# noisemaker_3-0.net
KiCad netlist of a schematic drawn in EAGLE
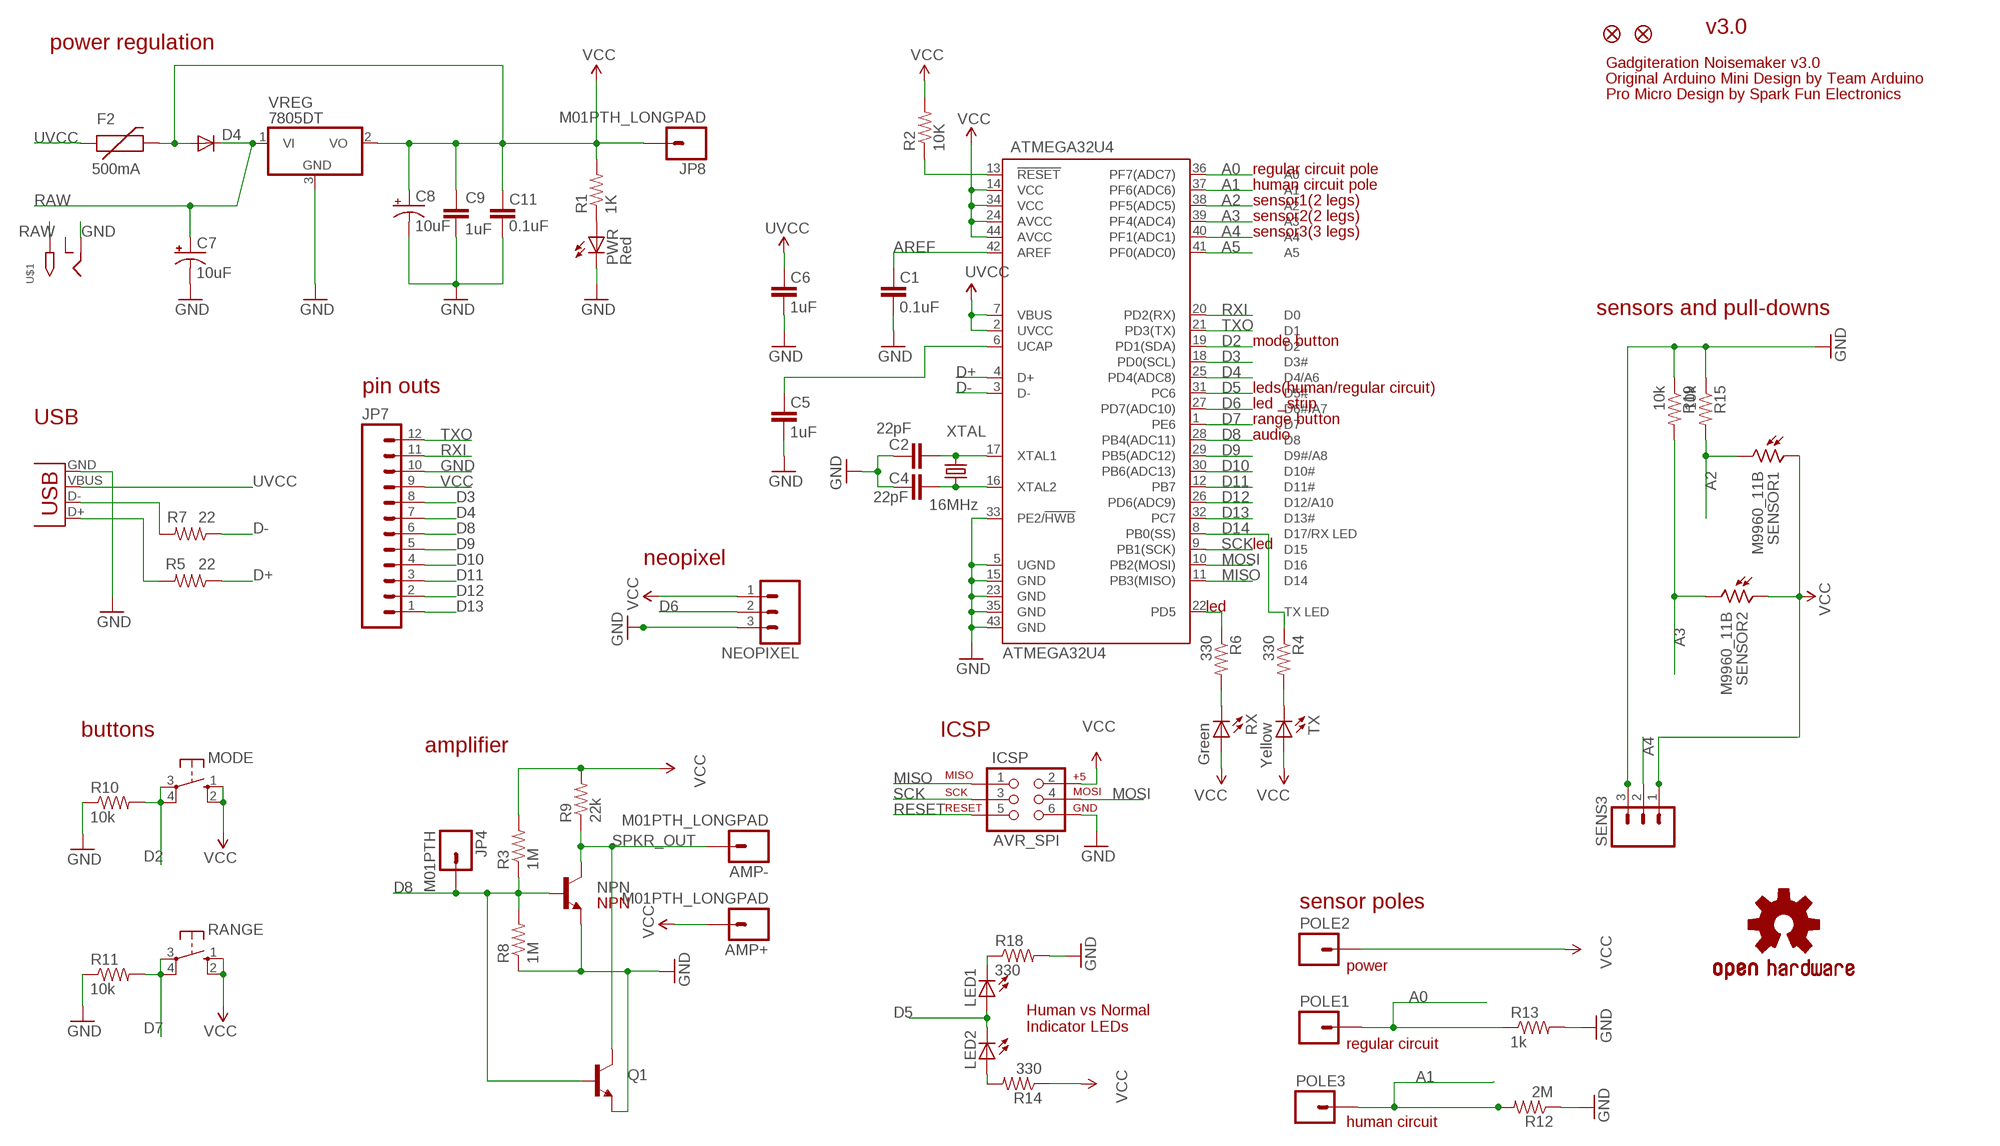
[diagram p0: schematic, sheet 1]

(export (version "E")
  (design (tool "Eeschema 10.0.6"))
  (components
    (comp (ref "AMP+")
      (value "M01PTH_LONGPAD")
      (footprint "eagle-import:1X01_LONGPAD")
      (libsource (lib "eagle-import") (part "M01PTH_LONGPAD"))
    )
    (comp (ref "AMP-")
      (value "M01PTH_LONGPAD")
      (footprint "eagle-import:1X01_LONGPAD")
      (libsource (lib "eagle-import") (part "M01PTH_LONGPAD"))
    )
    (comp (ref "ATMEGA32U4")
      (value "ATMEGA32U4")
      (footprint "eagle-import:SPARKFUN-DIGITALIC_TQFP44")
      (libsource (lib "eagle-import") (part "ATMEGA32U4TQFP"))
    )
    (comp (ref "C1")
      (value "0.1uF")
      (footprint "eagle-import:1206")
      (libsource (lib "eagle-import") (part "SparkFun-Capacitors_CAP1206"))
    )
    (comp (ref "C2")
      (value "22pF")
      (footprint "eagle-import:0603-CAP")
      (libsource (lib "eagle-import") (part "CAP0603-CAP"))
    )
    (comp (ref "C4")
      (value "22pF")
      (footprint "eagle-import:0603-CAP")
      (libsource (lib "eagle-import") (part "CAP0603-CAP"))
    )
    (comp (ref "C5")
      (value "1uF")
      (footprint "eagle-import:1206")
      (libsource (lib "eagle-import") (part "SparkFun-Capacitors_CAP1206"))
    )
    (comp (ref "C6")
      (value "1uF")
      (footprint "eagle-import:1206")
      (libsource (lib "eagle-import") (part "SparkFun-Capacitors_CAP1206"))
    )
    (comp (ref "C7")
      (value "10uF")
      (footprint "eagle-import:EIA3528-KIT")
      (libsource (lib "eagle-import") (part "CAP_POL3528-KIT"))
    )
    (comp (ref "C8")
      (value "10uF")
      (footprint "eagle-import:EIA3528-KIT")
      (libsource (lib "eagle-import") (part "CAP_POL3528-KIT"))
    )
    (comp (ref "C9")
      (value "1uF")
      (footprint "eagle-import:1206")
      (libsource (lib "eagle-import") (part "SparkFun-Capacitors_CAP1206"))
    )
    (comp (ref "C11")
      (value "0.1uF")
      (footprint "eagle-import:1206")
      (libsource (lib "eagle-import") (part "SparkFun-Capacitors_CAP1206"))
    )
    (comp (ref "D4")
      (value "DIODESOD")
      (footprint "eagle-import:SOD-323")
      (libsource (lib "eagle-import") (part "DIODESOD"))
    )
    (comp (ref "F2")
      (value "500mA")
      (footprint "eagle-import:PTC-1206")
      (libsource (lib "eagle-import") (part "PTCSMD"))
    )
    (comp (ref "ICSP")
      (value "AVR_SPI")
      (footprint "eagle-import:2X3")
      (libsource (lib "eagle-import") (part "AVR_SPI_PRG_6PTH"))
    )
    (comp (ref "JP1")
      (value "FIDUCIALUFIDUCIAL")
      (footprint "eagle-import:MICRO-FIDUCIAL")
      (libsource (lib "eagle-import") (part "FIDUCIALUFIDUCIAL"))
    )
    (comp (ref "JP2")
      (value "FIDUCIALUFIDUCIAL")
      (footprint "eagle-import:MICRO-FIDUCIAL")
      (libsource (lib "eagle-import") (part "FIDUCIALUFIDUCIAL"))
    )
    (comp (ref "JP3")
      (value "USB-B")
      (footprint "eagle-import:USB-B-PTH")
      (libsource (lib "eagle-import") (part "USBPTH"))
    )
    (comp (ref "JP4")
      (value "M01PTH")
      (footprint "eagle-import:1X01")
      (libsource (lib "eagle-import") (part "M01PTH"))
    )
    (comp (ref "JP7")
      (value "M12PTH")
      (footprint "eagle-import:1X12")
      (libsource (lib "eagle-import") (part "M12PTH"))
    )
    (comp (ref "JP8")
      (value "M01PTH_LONGPAD")
      (footprint "eagle-import:1X01_LONGPAD")
      (libsource (lib "eagle-import") (part "M01PTH_LONGPAD"))
    )
    (comp (ref "LED1")
      (value "LED3MM")
      (footprint "eagle-import:LED3MM")
      (libsource (lib "eagle-import") (part "LED3MM"))
    )
    (comp (ref "LED2")
      (value "LED3MM")
      (footprint "eagle-import:LED3MM")
      (libsource (lib "eagle-import") (part "LED3MM"))
    )
    (comp (ref "LOGO1")
      (value "OSHW-LOGOM")
      (footprint "eagle-import:OSHW-LOGO-M")
      (libsource (lib "eagle-import") (part "OSHW-LOGOM"))
    )
    (comp (ref "MODE")
      (value "10-XX")
      (footprint "eagle-import:B3F-10XX")
      (libsource (lib "eagle-import") (part "10-XX"))
    )
    (comp (ref "NEOPIXEL")
      (value "M03LONGPADS")
      (footprint "eagle-import:1X03_LONGPADS")
      (libsource (lib "eagle-import") (part "M03LONGPADS"))
    )
    (comp (ref "NPN")
      (value "TRANSISTOR_NPNSOT23-3")
      (footprint "eagle-import:SOT23-3")
      (libsource (lib "eagle-import") (part "TRANSISTOR_NPNSOT23-3"))
    )
    (comp (ref "POLE1")
      (value "M01PTH_LONGPAD")
      (footprint "eagle-import:1X01_LONGPAD")
      (libsource (lib "eagle-import") (part "M01PTH_LONGPAD"))
    )
    (comp (ref "POLE2")
      (value "M01PTH_LONGPAD")
      (footprint "eagle-import:1X01_LONGPAD")
      (libsource (lib "eagle-import") (part "M01PTH_LONGPAD"))
    )
    (comp (ref "POLE3")
      (value "M01PTH_LONGPAD")
      (footprint "eagle-import:1X01_LONGPAD")
      (libsource (lib "eagle-import") (part "M01PTH_LONGPAD"))
    )
    (comp (ref "PWR")
      (value "Red")
      (footprint "eagle-import:CHIPLED_1206")
      (libsource (lib "eagle-import") (part "LEDCHIPLED_1206"))
    )
    (comp (ref "Q1")
      (value "TRANSISTOR_NPNTO-92-AMMO")
      (footprint "eagle-import:TO-92-AMMO")
      (libsource (lib "eagle-import") (part "TRANSISTOR_NPNTO-92-AMMO"))
    )
    (comp (ref "R1")
      (value "1K")
      (footprint "eagle-import:1206")
      (libsource (lib "eagle-import") (part "RESISTOR1206"))
    )
    (comp (ref "R2")
      (value "10K")
      (footprint "eagle-import:1206")
      (libsource (lib "eagle-import") (part "RESISTOR1206"))
    )
    (comp (ref "R3")
      (value "1M")
      (footprint "eagle-import:1206")
      (libsource (lib "eagle-import") (part "RESISTOR1206"))
    )
    (comp (ref "R4")
      (value "330")
      (footprint "eagle-import:1206")
      (libsource (lib "eagle-import") (part "RESISTOR1206"))
    )
    (comp (ref "R5")
      (value "22")
      (footprint "eagle-import:1206")
      (libsource (lib "eagle-import") (part "RESISTOR1206"))
    )
    (comp (ref "R6")
      (value "330")
      (footprint "eagle-import:1206")
      (libsource (lib "eagle-import") (part "RESISTOR1206"))
    )
    (comp (ref "R7")
      (value "22")
      (footprint "eagle-import:1206")
      (libsource (lib "eagle-import") (part "RESISTOR1206"))
    )
    (comp (ref "R8")
      (value "1M")
      (footprint "eagle-import:1206")
      (libsource (lib "eagle-import") (part "RESISTOR1206"))
    )
    (comp (ref "R9")
      (value "22k")
      (footprint "eagle-import:1206")
      (libsource (lib "eagle-import") (part "RESISTOR1206"))
    )
    (comp (ref "R10")
      (value "10k")
      (footprint "eagle-import:1206")
      (libsource (lib "eagle-import") (part "RESISTOR1206"))
    )
    (comp (ref "R11")
      (value "10k")
      (footprint "eagle-import:1206")
      (libsource (lib "eagle-import") (part "RESISTOR1206"))
    )
    (comp (ref "R12")
      (value "2M")
      (footprint "eagle-import:1206")
      (libsource (lib "eagle-import") (part "RESISTOR1206"))
    )
    (comp (ref "R13")
      (value "1k")
      (footprint "eagle-import:1206")
      (libsource (lib "eagle-import") (part "RESISTOR1206"))
    )
    (comp (ref "R14")
      (value "330")
      (footprint "eagle-import:1206")
      (libsource (lib "eagle-import") (part "RESISTOR1206"))
    )
    (comp (ref "R15")
      (value "10k")
      (footprint "eagle-import:1206")
      (libsource (lib "eagle-import") (part "RESISTOR1206"))
    )
    (comp (ref "R18")
      (value "330")
      (footprint "eagle-import:1206")
      (libsource (lib "eagle-import") (part "RESISTOR1206"))
    )
    (comp (ref "R19")
      (value "10k")
      (footprint "eagle-import:1206")
      (libsource (lib "eagle-import") (part "RESISTOR1206"))
    )
    (comp (ref "RANGE")
      (value "10-XX")
      (footprint "eagle-import:B3F-10XX")
      (libsource (lib "eagle-import") (part "10-XX"))
    )
    (comp (ref "RX")
      (value "Green")
      (footprint "eagle-import:CHIPLED_1206")
      (libsource (lib "eagle-import") (part "LEDCHIPLED_1206"))
    )
    (comp (ref "SENS3")
      (value "M03POGO_PIN_HOLES_ONLY")
      (footprint "eagle-import:1X03_PP_HOLES_ONLY")
      (libsource (lib "eagle-import") (part "M03POGO_PIN_HOLES_ONLY"))
    )
    (comp (ref "SENSOR1")
      (value "M9960_11B")
      (footprint "eagle-import:M9960")
      (libsource (lib "eagle-import") (part "M9960_11B"))
    )
    (comp (ref "SENSOR2")
      (value "M9960_11B")
      (footprint "eagle-import:M9960")
      (libsource (lib "eagle-import") (part "M9960_11B"))
    )
    (comp (ref "TX")
      (value "Yellow")
      (footprint "eagle-import:CHIPLED_1206")
      (libsource (lib "eagle-import") (part "LEDCHIPLED_1206"))
    )
    (comp (ref "U$1")
      (value "2.1MMJACKTHM")
      (footprint "eagle-import:PJ-102A")
      (libsource (lib "eagle-import") (part "2.1MMJACKTHM"))
    )
    (comp (ref "VREG")
      (value "7805DT")
      (footprint "eagle-import:TO252")
      (libsource (lib "eagle-import") (part "78DT05"))
    )
    (comp (ref "XTAL")
      (value "16MHz")
      (footprint "eagle-import:CRYSTAL-SMD-5X3")
      (libsource (lib "eagle-import") (part "CRYSTAL5X3"))
    )
  )
  (nets
    (net (code "1") (name "/A0") (class "Default")
      (node (ref "ATMEGA32U4") (pin "36") (pinfunction "PF7(ADC7)_36") (pintype "bidirectional"))
      (node (ref "POLE1") (pin "1") (pinfunction "1_1") (pintype "passive"))
      (node (ref "R13") (pin "1") (pinfunction "1_1") (pintype "passive"))
    )
    (net (code "2") (name "/A1") (class "Default")
      (node (ref "ATMEGA32U4") (pin "37") (pinfunction "PF6(ADC6)_37") (pintype "bidirectional"))
      (node (ref "POLE3") (pin "1") (pinfunction "1_1") (pintype "passive"))
      (node (ref "R12") (pin "2") (pinfunction "2_2") (pintype "passive"))
    )
    (net (code "3") (name "/A2") (class "Default")
      (node (ref "ATMEGA32U4") (pin "38") (pinfunction "PF5(ADC5)_38") (pintype "bidirectional"))
      (node (ref "R15") (pin "2") (pinfunction "2_2") (pintype "passive"))
      (node (ref "SENSOR1") (pin "2") (pinfunction "2_2") (pintype "passive"))
    )
    (net (code "4") (name "/A3") (class "Default")
      (node (ref "ATMEGA32U4") (pin "39") (pinfunction "PF4(ADC4)_39") (pintype "bidirectional"))
      (node (ref "R19") (pin "2") (pinfunction "2_2") (pintype "passive"))
      (node (ref "SENSOR2") (pin "2") (pinfunction "2_2") (pintype "passive"))
    )
    (net (code "5") (name "/A4") (class "Default")
      (node (ref "ATMEGA32U4") (pin "40") (pinfunction "PF1(ADC1)_40") (pintype "bidirectional"))
      (node (ref "SENS3") (pin "2") (pinfunction "2_2") (pintype "passive"))
    )
    (net (code "6") (name "/A5") (class "Default")
      (node (ref "ATMEGA32U4") (pin "41") (pinfunction "PF0(ADC0)_41") (pintype "bidirectional"))
    )
    (net (code "7") (name "/AREF") (class "Default")
      (node (ref "ATMEGA32U4") (pin "42") (pinfunction "AREF_42") (pintype "bidirectional"))
      (node (ref "C1") (pin "2") (pinfunction "2_2") (pintype "passive"))
    )
    (net (code "8") (name "/D+") (class "Default")
      (node (ref "ATMEGA32U4") (pin "4") (pinfunction "D+_4") (pintype "bidirectional"))
      (node (ref "R5") (pin "1") (pinfunction "1_1") (pintype "passive"))
    )
    (net (code "9") (name "/D-") (class "Default")
      (node (ref "ATMEGA32U4") (pin "3") (pinfunction "D-_3") (pintype "bidirectional"))
      (node (ref "R7") (pin "1") (pinfunction "1_1") (pintype "passive"))
    )
    (net (code "10") (name "/D2") (class "Default")
      (node (ref "ATMEGA32U4") (pin "19") (pinfunction "PD1(SDA)_19") (pintype "bidirectional"))
      (node (ref "MODE") (pin "3") (pinfunction "P_3") (pintype "passive"))
      (node (ref "MODE") (pin "4") (pinfunction "P1_4") (pintype "passive"))
      (node (ref "R10") (pin "2") (pinfunction "2_2") (pintype "passive"))
    )
    (net (code "11") (name "/D3") (class "Default")
      (node (ref "ATMEGA32U4") (pin "18") (pinfunction "PD0(SCL)_18") (pintype "bidirectional"))
      (node (ref "JP7") (pin "8") (pinfunction "8_8") (pintype "passive"))
    )
    (net (code "12") (name "/D4") (class "Default")
      (node (ref "ATMEGA32U4") (pin "25") (pinfunction "PD4(ADC8)_25") (pintype "bidirectional"))
      (node (ref "JP7") (pin "7") (pinfunction "7_7") (pintype "passive"))
    )
    (net (code "13") (name "/D5") (class "Default")
      (node (ref "ATMEGA32U4") (pin "31") (pinfunction "PC6_31") (pintype "bidirectional"))
      (node (ref "LED1") (pin "A") (pinfunction "A_A") (pintype "passive"))
      (node (ref "LED2") (pin "K") (pinfunction "C_K") (pintype "passive"))
    )
    (net (code "14") (name "/D6") (class "Default")
      (node (ref "ATMEGA32U4") (pin "27") (pinfunction "PD7(ADC10)_27") (pintype "bidirectional"))
      (node (ref "NEOPIXEL") (pin "2") (pinfunction "2_2") (pintype "passive"))
    )
    (net (code "15") (name "/D7") (class "Default")
      (node (ref "ATMEGA32U4") (pin "1") (pinfunction "PE6_1") (pintype "bidirectional"))
      (node (ref "R11") (pin "2") (pinfunction "2_2") (pintype "passive"))
      (node (ref "RANGE") (pin "3") (pinfunction "P_3") (pintype "passive"))
      (node (ref "RANGE") (pin "4") (pinfunction "P1_4") (pintype "passive"))
    )
    (net (code "16") (name "/D8") (class "Default")
      (node (ref "ATMEGA32U4") (pin "28") (pinfunction "PB4(ADC11)_28") (pintype "bidirectional"))
      (node (ref "JP4") (pin "1") (pinfunction "1_1") (pintype "passive"))
      (node (ref "JP7") (pin "6") (pinfunction "6_6") (pintype "passive"))
      (node (ref "NPN") (pin "1") (pinfunction "B_1") (pintype "passive"))
      (node (ref "Q1") (pin "2") (pinfunction "B_2") (pintype "passive"))
      (node (ref "R3") (pin "1") (pinfunction "1_1") (pintype "passive"))
      (node (ref "R8") (pin "2") (pinfunction "2_2") (pintype "passive"))
    )
    (net (code "17") (name "/D9") (class "Default")
      (node (ref "ATMEGA32U4") (pin "29") (pinfunction "PB5(ADC12)_29") (pintype "bidirectional"))
      (node (ref "JP7") (pin "5") (pinfunction "5_5") (pintype "passive"))
    )
    (net (code "18") (name "/D10") (class "Default")
      (node (ref "ATMEGA32U4") (pin "30") (pinfunction "PB6(ADC13)_30") (pintype "bidirectional"))
      (node (ref "JP7") (pin "4") (pinfunction "4_4") (pintype "passive"))
    )
    (net (code "19") (name "/D11") (class "Default")
      (node (ref "ATMEGA32U4") (pin "12") (pinfunction "PB7_12") (pintype "bidirectional"))
      (node (ref "JP7") (pin "3") (pinfunction "3_3") (pintype "passive"))
    )
    (net (code "20") (name "/D12") (class "Default")
      (node (ref "ATMEGA32U4") (pin "26") (pinfunction "PD6(ADC9)_26") (pintype "bidirectional"))
      (node (ref "JP7") (pin "2") (pinfunction "2_2") (pintype "passive"))
    )
    (net (code "21") (name "/D13") (class "Default")
      (node (ref "ATMEGA32U4") (pin "32") (pinfunction "PC7_32") (pintype "bidirectional"))
      (node (ref "JP7") (pin "1") (pinfunction "1_1") (pintype "passive"))
    )
    (net (code "22") (name "/D14") (class "Default")
      (node (ref "ATMEGA32U4") (pin "8") (pinfunction "PB0(SS)_8") (pintype "bidirectional"))
      (node (ref "R4") (pin "1") (pinfunction "1_1") (pintype "passive"))
    )
    (net (code "23") (name "/MISO") (class "Default")
      (node (ref "ATMEGA32U4") (pin "11") (pinfunction "PB3(MISO)_11") (pintype "bidirectional"))
      (node (ref "ICSP") (pin "1") (pinfunction "1_1") (pintype "passive"))
    )
    (net (code "24") (name "/MOSI") (class "Default")
      (node (ref "ATMEGA32U4") (pin "10") (pinfunction "PB2(MOSI)_10") (pintype "bidirectional"))
      (node (ref "ICSP") (pin "4") (pinfunction "4_4") (pintype "passive"))
    )
    (net (code "25") (name "/RAW") (class "Default")
      (node (ref "C7") (pin "A") (pinfunction "+_A") (pintype "passive"))
      (node (ref "D4") (pin "1") (pinfunction "C_1") (pintype "passive"))
      (node (ref "U$1") (pin "TIP") (pinfunction "TIP_TIP") (pintype "bidirectional"))
      (node (ref "VREG") (pin "1") (pinfunction "VI_1") (pintype "input"))
    )
    (net (code "26") (name "/RESET") (class "Default")
      (node (ref "ATMEGA32U4") (pin "13") (pinfunction "~{RESET}_13") (pintype "bidirectional"))
      (node (ref "ICSP") (pin "5") (pinfunction "5_5") (pintype "passive"))
      (node (ref "R2") (pin "1") (pinfunction "1_1") (pintype "passive"))
    )
    (net (code "27") (name "/RXI") (class "Default")
      (node (ref "ATMEGA32U4") (pin "20") (pinfunction "PD2(RX)_20") (pintype "bidirectional"))
      (node (ref "JP7") (pin "11") (pinfunction "11_11") (pintype "passive"))
    )
    (net (code "28") (name "/SCK") (class "Default")
      (node (ref "ATMEGA32U4") (pin "9") (pinfunction "PB1(SCK)_9") (pintype "bidirectional"))
      (node (ref "ICSP") (pin "3") (pinfunction "3_3") (pintype "passive"))
    )
    (net (code "29") (name "/SPKR_OUT") (class "Default")
      (node (ref "AMP-") (pin "1") (pinfunction "1_1") (pintype "passive"))
      (node (ref "NPN") (pin "3") (pinfunction "C_3") (pintype "passive"))
      (node (ref "Q1") (pin "3") (pinfunction "C_3") (pintype "passive"))
      (node (ref "R9") (pin "1") (pinfunction "1_1") (pintype "passive"))
    )
    (net (code "30") (name "/TXO") (class "Default")
      (node (ref "ATMEGA32U4") (pin "21") (pinfunction "PD3(TX)_21") (pintype "bidirectional"))
      (node (ref "JP7") (pin "12") (pinfunction "12_12") (pintype "passive"))
    )
    (net (code "31") (name "GND") (class "Default")
      (node (ref "ATMEGA32U4") (pin "15") (pinfunction "GND_15") (pintype "bidirectional"))
      (node (ref "ATMEGA32U4") (pin "23") (pinfunction "GND_23") (pintype "bidirectional"))
      (node (ref "ATMEGA32U4") (pin "33") (pinfunction "PE2/~{HWB}_33") (pintype "bidirectional"))
      (node (ref "ATMEGA32U4") (pin "35") (pinfunction "GND_35") (pintype "bidirectional"))
      (node (ref "ATMEGA32U4") (pin "43") (pinfunction "GND_43") (pintype "bidirectional"))
      (node (ref "ATMEGA32U4") (pin "5") (pinfunction "UGND_5") (pintype "bidirectional"))
      (node (ref "C1") (pin "1") (pinfunction "1_1") (pintype "passive"))
      (node (ref "C11") (pin "1") (pinfunction "1_1") (pintype "passive"))
      (node (ref "C2") (pin "2") (pinfunction "2_2") (pintype "passive"))
      (node (ref "C4") (pin "2") (pinfunction "2_2") (pintype "passive"))
      (node (ref "C5") (pin "1") (pinfunction "1_1") (pintype "passive"))
      (node (ref "C6") (pin "1") (pinfunction "1_1") (pintype "passive"))
      (node (ref "C7") (pin "C") (pinfunction "-_C") (pintype "passive"))
      (node (ref "C8") (pin "C") (pinfunction "-_C") (pintype "passive"))
      (node (ref "C9") (pin "2") (pinfunction "2_2") (pintype "passive"))
      (node (ref "ICSP") (pin "6") (pinfunction "6_6") (pintype "passive"))
      (node (ref "JP3") (pin "GND") (pinfunction "GND_GND") (pintype "bidirectional"))
      (node (ref "JP7") (pin "10") (pinfunction "10_10") (pintype "passive"))
      (node (ref "NEOPIXEL") (pin "3") (pinfunction "3_3") (pintype "passive"))
      (node (ref "NPN") (pin "2") (pinfunction "E_2") (pintype "passive"))
      (node (ref "PWR") (pin "C") (pinfunction "C_C") (pintype "passive"))
      (node (ref "Q1") (pin "1") (pinfunction "E_1") (pintype "passive"))
      (node (ref "R10") (pin "1") (pinfunction "1_1") (pintype "passive"))
      (node (ref "R11") (pin "1") (pinfunction "1_1") (pintype "passive"))
      (node (ref "R12") (pin "1") (pinfunction "1_1") (pintype "passive"))
      (node (ref "R13") (pin "2") (pinfunction "2_2") (pintype "passive"))
      (node (ref "R15") (pin "1") (pinfunction "1_1") (pintype "passive"))
      (node (ref "R18") (pin "2") (pinfunction "2_2") (pintype "passive"))
      (node (ref "R19") (pin "1") (pinfunction "1_1") (pintype "passive"))
      (node (ref "R8") (pin "1") (pinfunction "1_1") (pintype "passive"))
      (node (ref "SENS3") (pin "3") (pinfunction "3_3") (pintype "passive"))
      (node (ref "U$1") (pin "RING") (pinfunction "RING_RING") (pintype "bidirectional"))
      (node (ref "VREG") (pin "3") (pinfunction "GND_3") (pintype "passive"))
    )
    (net (code "32") (name "Net-(ATMEGA32U4-PD5)") (class "Default")
      (node (ref "ATMEGA32U4") (pin "22") (pinfunction "PD5_22") (pintype "bidirectional"))
      (node (ref "R6") (pin "1") (pinfunction "1_1") (pintype "passive"))
    )
    (net (code "33") (name "Net-(ATMEGA32U4-UCAP)") (class "Default")
      (node (ref "ATMEGA32U4") (pin "6") (pinfunction "UCAP_6") (pintype "bidirectional"))
      (node (ref "C5") (pin "2") (pinfunction "2_2") (pintype "passive"))
    )
    (net (code "34") (name "Net-(ATMEGA32U4-XTAL1)") (class "Default")
      (node (ref "ATMEGA32U4") (pin "17") (pinfunction "XTAL1_17") (pintype "bidirectional"))
      (node (ref "C2") (pin "1") (pinfunction "1_1") (pintype "passive"))
      (node (ref "XTAL") (pin "3") (pinfunction "2_3") (pintype "passive"))
    )
    (net (code "35") (name "Net-(ATMEGA32U4-XTAL2)") (class "Default")
      (node (ref "ATMEGA32U4") (pin "16") (pinfunction "XTAL2_16") (pintype "bidirectional"))
      (node (ref "C4") (pin "1") (pinfunction "1_1") (pintype "passive"))
      (node (ref "XTAL") (pin "1") (pinfunction "1_1") (pintype "passive"))
    )
    (net (code "36") (name "Net-(JP3-PadD+)") (class "Default")
      (node (ref "JP3") (pin "D+") (pinfunction "D+_D+") (pintype "bidirectional"))
      (node (ref "R5") (pin "2") (pinfunction "2_2") (pintype "passive"))
    )
    (net (code "37") (name "Net-(JP3-PadD-)") (class "Default")
      (node (ref "JP3") (pin "D-") (pinfunction "D-_D-") (pintype "bidirectional"))
      (node (ref "R7") (pin "2") (pinfunction "2_2") (pintype "passive"))
    )
    (net (code "38") (name "Net-(LED1-C)") (class "Default")
      (node (ref "LED1") (pin "K") (pinfunction "C_K") (pintype "passive"))
      (node (ref "R18") (pin "1") (pinfunction "1_1") (pintype "passive"))
    )
    (net (code "39") (name "Net-(LED2-PadA)") (class "Default")
      (node (ref "LED2") (pin "A") (pinfunction "A_A") (pintype "passive"))
      (node (ref "R14") (pin "2") (pinfunction "2_2") (pintype "passive"))
    )
    (net (code "40") (name "Net-(PWR-PadA)") (class "Default")
      (node (ref "PWR") (pin "A") (pinfunction "A_A") (pintype "passive"))
      (node (ref "R1") (pin "1") (pinfunction "1_1") (pintype "passive"))
    )
    (net (code "41") (name "Net-(R4-Pad2)") (class "Default")
      (node (ref "R4") (pin "2") (pinfunction "2_2") (pintype "passive"))
      (node (ref "TX") (pin "C") (pinfunction "C_C") (pintype "passive"))
    )
    (net (code "42") (name "Net-(R6-Pad2)") (class "Default")
      (node (ref "R6") (pin "2") (pinfunction "2_2") (pintype "passive"))
      (node (ref "RX") (pin "C") (pinfunction "C_C") (pintype "passive"))
    )
    (net (code "43") (name "UVCC") (class "Default")
      (node (ref "ATMEGA32U4") (pin "2") (pinfunction "UVCC_2") (pintype "bidirectional"))
      (node (ref "ATMEGA32U4") (pin "7") (pinfunction "VBUS_7") (pintype "bidirectional"))
      (node (ref "C6") (pin "2") (pinfunction "2_2") (pintype "passive"))
      (node (ref "F2") (pin "1") (pinfunction "1_1") (pintype "bidirectional"))
      (node (ref "JP3") (pin "VBUS") (pinfunction "VBUS_VBUS") (pintype "bidirectional"))
    )
    (net (code "44") (name "VCC") (class "Default")
      (node (ref "AMP+") (pin "1") (pinfunction "1_1") (pintype "passive"))
      (node (ref "ATMEGA32U4") (pin "14") (pinfunction "VCC_14") (pintype "bidirectional"))
      (node (ref "ATMEGA32U4") (pin "24") (pinfunction "AVCC_24") (pintype "bidirectional"))
      (node (ref "ATMEGA32U4") (pin "34") (pinfunction "VCC_34") (pintype "bidirectional"))
      (node (ref "ATMEGA32U4") (pin "44") (pinfunction "AVCC_44") (pintype "bidirectional"))
      (node (ref "C11") (pin "2") (pinfunction "2_2") (pintype "passive"))
      (node (ref "C8") (pin "A") (pinfunction "+_A") (pintype "passive"))
      (node (ref "C9") (pin "1") (pinfunction "1_1") (pintype "passive"))
      (node (ref "D4") (pin "2") (pinfunction "A_2") (pintype "passive"))
      (node (ref "F2") (pin "2") (pinfunction "2_2") (pintype "bidirectional"))
      (node (ref "ICSP") (pin "2") (pinfunction "2_2") (pintype "passive"))
      (node (ref "JP7") (pin "9") (pinfunction "9_9") (pintype "passive"))
      (node (ref "JP8") (pin "1") (pinfunction "1_1") (pintype "passive"))
      (node (ref "MODE") (pin "1") (pinfunction "S_1") (pintype "passive"))
      (node (ref "MODE") (pin "2") (pinfunction "S1_2") (pintype "passive"))
      (node (ref "NEOPIXEL") (pin "1") (pinfunction "1_1") (pintype "passive"))
      (node (ref "POLE2") (pin "1") (pinfunction "1_1") (pintype "passive"))
      (node (ref "R1") (pin "2") (pinfunction "2_2") (pintype "passive"))
      (node (ref "R14") (pin "1") (pinfunction "1_1") (pintype "passive"))
      (node (ref "R2") (pin "2") (pinfunction "2_2") (pintype "passive"))
      (node (ref "R3") (pin "2") (pinfunction "2_2") (pintype "passive"))
      (node (ref "R9") (pin "2") (pinfunction "2_2") (pintype "passive"))
      (node (ref "RANGE") (pin "1") (pinfunction "S_1") (pintype "passive"))
      (node (ref "RANGE") (pin "2") (pinfunction "S1_2") (pintype "passive"))
      (node (ref "RX") (pin "A") (pinfunction "A_A") (pintype "passive"))
      (node (ref "SENS3") (pin "1") (pinfunction "1_1") (pintype "passive"))
      (node (ref "SENSOR1") (pin "1") (pinfunction "1_1") (pintype "passive"))
      (node (ref "SENSOR2") (pin "1") (pinfunction "1_1") (pintype "passive"))
      (node (ref "TX") (pin "A") (pinfunction "A_A") (pintype "passive"))
      (node (ref "VREG") (pin "2") (pinfunction "VO_2") (pintype "passive"))
    )
    (net (code "45") (name "unconnected-(U$1-PadRING_SW)") (class "Default")
      (node (ref "U$1") (pin "RING_SW") (pinfunction "RING_SW_RING_SW") (pintype "bidirectional"))
    )
  )
)
